# 09_Memory.net
KiCad netlist of a schematic drawn in Altium Designer
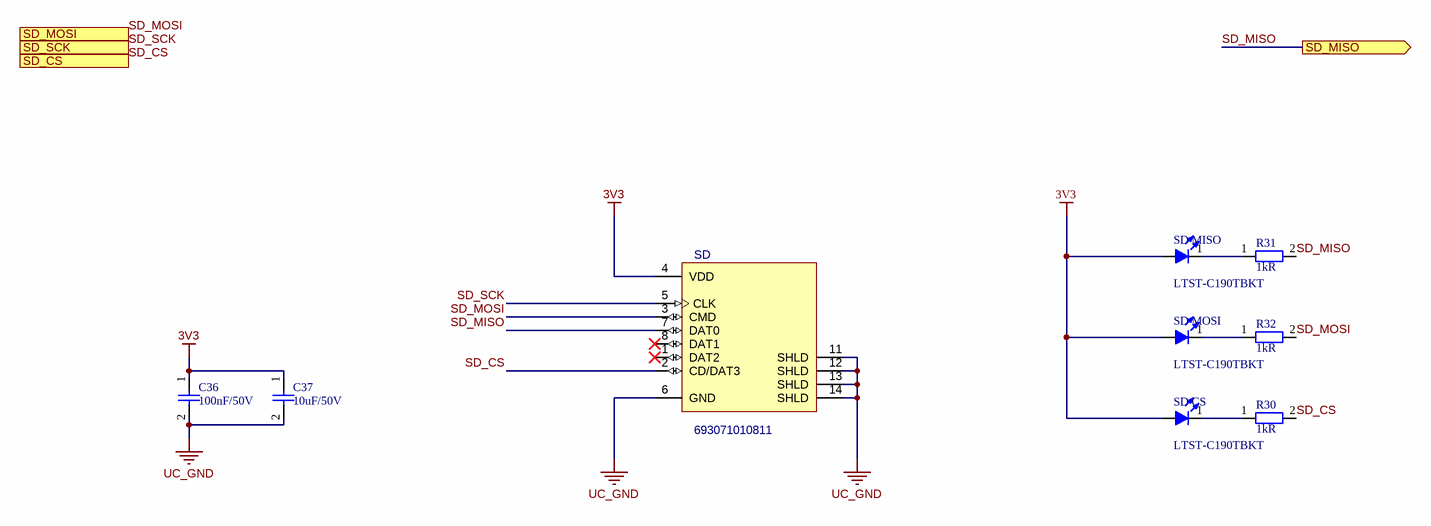
[diagram p0: 09_Memory.SchDoc]

(export (version "E")
  (design (tool "Eeschema 10.0.6"))
  (components
    (comp (ref "C36")
      (value "100nF/50V")
      (footprint "CAPC1005X05L")
      (description "Cap MLCC, 100nF, 50V, X7R, 10%, 0402")
      (fields (field (name "TOLERANCE") "10%"))
      (libsource (lib "Altium Concord Pro on Altium 365") (part "CAP-NP-2"))
    )
    (comp (ref "C37")
      (value "10uF/50V")
      (footprint "CAPC3216X12L")
      (description "Cap MLCC, 10uF, 50V, X5R, 10%, 1206")
      (fields (field (name "TOLERANCE") "10%"))
      (libsource (lib "Altium Concord Pro on Altium 365") (part "CAP-NP-2"))
    )
    (comp (ref "R30")
      (value "1kR")
      (footprint "RESC1005X04L")
      (description "Res, 1kR, 1%, 0.1W, 0402")
      (fields (field (name "POWER") "100mW") (field (name "TOLERANCE") "1%"))
      (libsource (lib "Altium Concord Pro on Altium 365") (part "RES-2"))
    )
    (comp (ref "R31")
      (value "1kR")
      (footprint "RESC1005X04L")
      (description "Res, 1kR, 1%, 0.1W, 0402")
      (fields (field (name "POWER") "100mW") (field (name "TOLERANCE") "1%"))
      (libsource (lib "Altium Concord Pro on Altium 365") (part "RES-2"))
    )
    (comp (ref "R32")
      (value "1kR")
      (footprint "RESC1005X04L")
      (description "Res, 1kR, 1%, 0.1W, 0402")
      (fields (field (name "POWER") "100mW") (field (name "TOLERANCE") "1%"))
      (libsource (lib "Altium Concord Pro on Altium 365") (part "RES-2"))
    )
    (comp (ref "SD")
      (value "693071010811")
      (footprint "WUERTH_693071010811")
      (description "SD-Card Micro Connector, 8 Position, Push In, Push Out, SMD")
      (fields (field (name "MANUFACTURER") "Würth"))
      (libsource (lib "Altium Concord Pro on Altium 365") (part "CON_SDCARD_MICRO"))
    )
    (comp (ref "SD CS")
      (value "LTST-C190TBKT")
      (footprint "LEDSC160X80X80-2Lbl")
      (description "LED, Blue, 20mA, 2.8V, 0603")
      (libsource (lib "Altium Concord Pro on Altium 365") (part "LED-BLUE-AK-2"))
    )
    (comp (ref "SD MISO")
      (value "LTST-C190TBKT")
      (footprint "LEDSC160X80X80-2Lbl")
      (description "LED, Blue, 20mA, 2.8V, 0603")
      (libsource (lib "Altium Concord Pro on Altium 365") (part "LED-BLUE-AK-2"))
    )
    (comp (ref "SD MOSI")
      (value "LTST-C190TBKT")
      (footprint "LEDSC160X80X80-2Lbl")
      (description "LED, Blue, 20mA, 2.8V, 0603")
      (libsource (lib "Altium Concord Pro on Altium 365") (part "LED-BLUE-AK-2"))
    )
  )
  (nets
    (net (code "1") (name "/SD_CS") (class "Default")
      (node (ref "R30") (pin "2") (pinfunction "2_2") (pintype "passive"))
      (node (ref "SD") (pin "2") (pinfunction "CD/DAT3_2") (pintype "bidirectional"))
    )
    (net (code "2") (name "/SD_MISO") (class "Default")
      (node (ref "R31") (pin "2") (pinfunction "2_2") (pintype "passive"))
      (node (ref "SD") (pin "7") (pinfunction "DAT0_7") (pintype "bidirectional"))
    )
    (net (code "3") (name "/SD_MOSI") (class "Default")
      (node (ref "R32") (pin "2") (pinfunction "2_2") (pintype "passive"))
      (node (ref "SD") (pin "3") (pinfunction "CMD_3") (pintype "bidirectional"))
    )
    (net (code "4") (name "/SD_SCK") (class "Default")
      (node (ref "SD") (pin "5") (pinfunction "CLK_5") (pintype "input"))
    )
    (net (code "5") (name "3V3") (class "Default")
      (node (ref "C36") (pin "1") (pinfunction "1_1") (pintype "passive"))
      (node (ref "C37") (pin "1") (pinfunction "1_1") (pintype "passive"))
      (node (ref "SD") (pin "4") (pinfunction "VDD_4") (pintype "power_in"))
      (node (ref "SD CS") (pin "2") (pinfunction "A_2") (pintype "passive"))
      (node (ref "SD MISO") (pin "2") (pinfunction "A_2") (pintype "passive"))
      (node (ref "SD MOSI") (pin "2") (pinfunction "A_2") (pintype "passive"))
    )
    (net (code "6") (name "Net-(SD CS-K)") (class "Default")
      (node (ref "R30") (pin "1") (pinfunction "1_1") (pintype "passive"))
      (node (ref "SD CS") (pin "1") (pinfunction "K_1") (pintype "passive"))
    )
    (net (code "7") (name "Net-(SD MISO-K)") (class "Default")
      (node (ref "R31") (pin "1") (pinfunction "1_1") (pintype "passive"))
      (node (ref "SD MISO") (pin "1") (pinfunction "K_1") (pintype "passive"))
    )
    (net (code "8") (name "Net-(SD MOSI-K)") (class "Default")
      (node (ref "R32") (pin "1") (pinfunction "1_1") (pintype "passive"))
      (node (ref "SD MOSI") (pin "1") (pinfunction "K_1") (pintype "passive"))
    )
    (net (code "9") (name "UC_GND") (class "Default")
      (node (ref "C36") (pin "2") (pinfunction "2_2") (pintype "passive"))
      (node (ref "C37") (pin "2") (pinfunction "2_2") (pintype "passive"))
      (node (ref "SD") (pin "11") (pinfunction "SHLD_11") (pintype "passive"))
      (node (ref "SD") (pin "12") (pinfunction "SHLD_12") (pintype "passive"))
      (node (ref "SD") (pin "13") (pinfunction "SHLD_13") (pintype "passive"))
      (node (ref "SD") (pin "14") (pinfunction "SHLD_14") (pintype "passive"))
      (node (ref "SD") (pin "6") (pinfunction "GND_6") (pintype "passive"))
    )
    (net (code "10") (name "unconnected-(SD-DAT1-Pad8)") (class "Default")
      (node (ref "SD") (pin "8") (pinfunction "DAT1_8") (pintype "bidirectional+no_connect"))
    )
    (net (code "11") (name "unconnected-(SD-DAT2-Pad1)") (class "Default")
      (node (ref "SD") (pin "1") (pinfunction "DAT2_1") (pintype "bidirectional+no_connect"))
    )
  )
)
